# led.net
KiCad netlist of a schematic drawn in Altium Designer
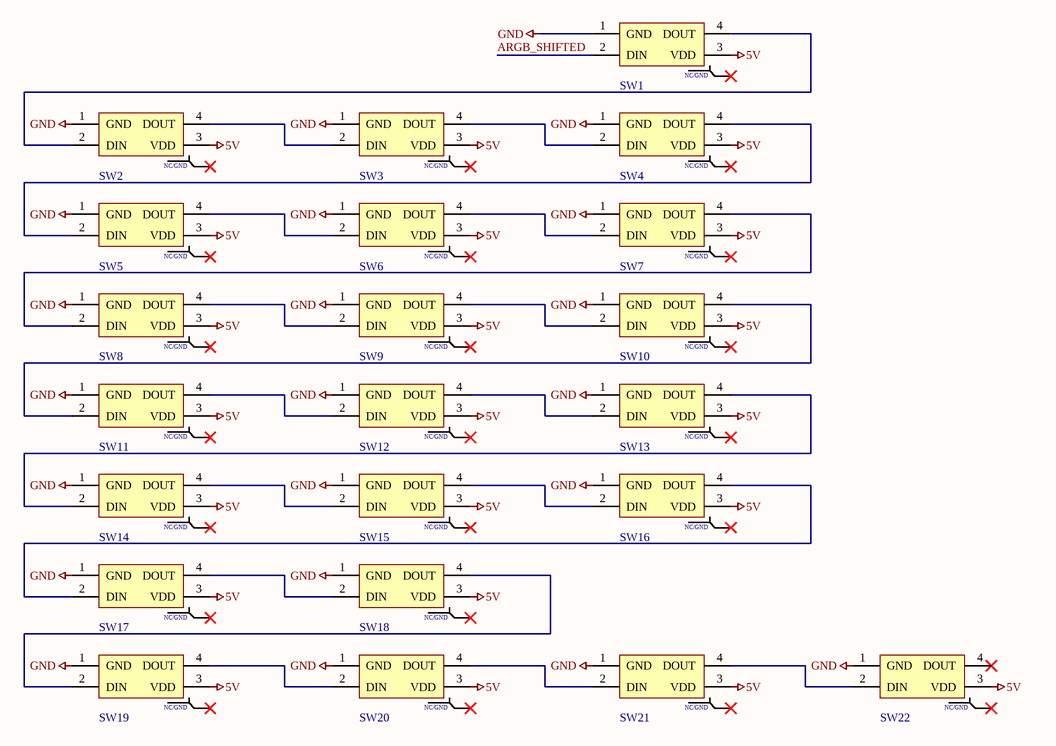
[diagram p0: led.SchDoc]

(export (version "E")
  (design (tool "Eeschema 10.0.6"))
  (components
    (comp (ref "SW1")
      (value "Switch")
      (footprint "Switch")
      (description "Gateron Magnetic Jade Switch")
      (libsource (lib "CHOCO_KEYBOARD") (part "Switch"))
    )
    (comp (ref "SW2")
      (value "Switch")
      (footprint "Switch")
      (description "Gateron Magnetic Jade Switch")
      (libsource (lib "CHOCO_KEYBOARD") (part "Switch"))
    )
    (comp (ref "SW3")
      (value "Switch")
      (footprint "Switch")
      (description "Gateron Magnetic Jade Switch")
      (libsource (lib "CHOCO_KEYBOARD") (part "Switch"))
    )
    (comp (ref "SW4")
      (value "Switch")
      (footprint "Switch")
      (description "Gateron Magnetic Jade Switch")
      (libsource (lib "CHOCO_KEYBOARD") (part "Switch"))
    )
    (comp (ref "SW5")
      (value "Switch")
      (footprint "Switch")
      (description "Gateron Magnetic Jade Switch")
      (libsource (lib "CHOCO_KEYBOARD") (part "Switch"))
    )
    (comp (ref "SW6")
      (value "Switch")
      (footprint "Switch")
      (description "Gateron Magnetic Jade Switch")
      (libsource (lib "CHOCO_KEYBOARD") (part "Switch"))
    )
    (comp (ref "SW7")
      (value "Switch")
      (footprint "Switch")
      (description "Gateron Magnetic Jade Switch")
      (libsource (lib "CHOCO_KEYBOARD") (part "Switch"))
    )
    (comp (ref "SW8")
      (value "Switch")
      (footprint "Switch")
      (description "Gateron Magnetic Jade Switch")
      (libsource (lib "CHOCO_KEYBOARD") (part "Switch"))
    )
    (comp (ref "SW9")
      (value "Switch")
      (footprint "Switch")
      (description "Gateron Magnetic Jade Switch")
      (libsource (lib "CHOCO_KEYBOARD") (part "Switch"))
    )
    (comp (ref "SW10")
      (value "Switch")
      (footprint "Switch")
      (description "Gateron Magnetic Jade Switch")
      (libsource (lib "CHOCO_KEYBOARD") (part "Switch"))
    )
    (comp (ref "SW11")
      (value "Switch")
      (footprint "Switch")
      (description "Gateron Magnetic Jade Switch")
      (libsource (lib "CHOCO_KEYBOARD") (part "Switch"))
    )
    (comp (ref "SW12")
      (value "Switch")
      (footprint "Switch")
      (description "Gateron Magnetic Jade Switch")
      (libsource (lib "CHOCO_KEYBOARD") (part "Switch"))
    )
    (comp (ref "SW13")
      (value "Switch")
      (footprint "Switch")
      (description "Gateron Magnetic Jade Switch")
      (libsource (lib "CHOCO_KEYBOARD") (part "Switch"))
    )
    (comp (ref "SW14")
      (value "Switch")
      (footprint "Switch")
      (description "Gateron Magnetic Jade Switch")
      (libsource (lib "CHOCO_KEYBOARD") (part "Switch"))
    )
    (comp (ref "SW15")
      (value "Switch")
      (footprint "Switch")
      (description "Gateron Magnetic Jade Switch")
      (libsource (lib "CHOCO_KEYBOARD") (part "Switch"))
    )
    (comp (ref "SW16")
      (value "Switch")
      (footprint "Switch")
      (description "Gateron Magnetic Jade Switch")
      (libsource (lib "CHOCO_KEYBOARD") (part "Switch"))
    )
    (comp (ref "SW17")
      (value "Switch")
      (footprint "Switch")
      (description "Gateron Magnetic Jade Switch")
      (libsource (lib "CHOCO_KEYBOARD") (part "Switch"))
    )
    (comp (ref "SW18")
      (value "Switch")
      (footprint "Switch")
      (description "Gateron Magnetic Jade Switch")
      (libsource (lib "CHOCO_KEYBOARD") (part "Switch"))
    )
    (comp (ref "SW19")
      (value "Switch")
      (footprint "Switch")
      (description "Gateron Magnetic Jade Switch")
      (libsource (lib "CHOCO_KEYBOARD") (part "Switch"))
    )
    (comp (ref "SW20")
      (value "Switch")
      (footprint "Switch")
      (description "Gateron Magnetic Jade Switch")
      (libsource (lib "CHOCO_KEYBOARD") (part "Switch"))
    )
    (comp (ref "SW21")
      (value "Switch")
      (footprint "Switch")
      (description "Gateron Magnetic Jade Switch")
      (libsource (lib "CHOCO_KEYBOARD") (part "Switch"))
    )
    (comp (ref "SW22")
      (value "Switch")
      (footprint "Switch")
      (description "Gateron Magnetic Jade Switch")
      (libsource (lib "CHOCO_KEYBOARD") (part "Switch"))
    )
  )
  (nets
    (net (code "1") (name "/ARGB_SHIFTED") (class "Default")
      (node (ref "SW1") (pin "2") (pinfunction "DIN_2") (pintype "passive"))
    )
    (net (code "2") (name "5V") (class "Default")
      (node (ref "SW1") (pin "3") (pinfunction "VDD_3") (pintype "passive"))
      (node (ref "SW10") (pin "3") (pinfunction "VDD_3") (pintype "passive"))
      (node (ref "SW11") (pin "3") (pinfunction "VDD_3") (pintype "passive"))
      (node (ref "SW12") (pin "3") (pinfunction "VDD_3") (pintype "passive"))
      (node (ref "SW13") (pin "3") (pinfunction "VDD_3") (pintype "passive"))
      (node (ref "SW14") (pin "3") (pinfunction "VDD_3") (pintype "passive"))
      (node (ref "SW15") (pin "3") (pinfunction "VDD_3") (pintype "passive"))
      (node (ref "SW16") (pin "3") (pinfunction "VDD_3") (pintype "passive"))
      (node (ref "SW17") (pin "3") (pinfunction "VDD_3") (pintype "passive"))
      (node (ref "SW18") (pin "3") (pinfunction "VDD_3") (pintype "passive"))
      (node (ref "SW19") (pin "3") (pinfunction "VDD_3") (pintype "passive"))
      (node (ref "SW2") (pin "3") (pinfunction "VDD_3") (pintype "passive"))
      (node (ref "SW20") (pin "3") (pinfunction "VDD_3") (pintype "passive"))
      (node (ref "SW21") (pin "3") (pinfunction "VDD_3") (pintype "passive"))
      (node (ref "SW22") (pin "3") (pinfunction "VDD_3") (pintype "passive"))
      (node (ref "SW3") (pin "3") (pinfunction "VDD_3") (pintype "passive"))
      (node (ref "SW4") (pin "3") (pinfunction "VDD_3") (pintype "passive"))
      (node (ref "SW5") (pin "3") (pinfunction "VDD_3") (pintype "passive"))
      (node (ref "SW6") (pin "3") (pinfunction "VDD_3") (pintype "passive"))
      (node (ref "SW7") (pin "3") (pinfunction "VDD_3") (pintype "passive"))
      (node (ref "SW8") (pin "3") (pinfunction "VDD_3") (pintype "passive"))
      (node (ref "SW9") (pin "3") (pinfunction "VDD_3") (pintype "passive"))
    )
    (net (code "3") (name "GND") (class "Default")
      (node (ref "SW1") (pin "1") (pinfunction "GND_1") (pintype "passive"))
      (node (ref "SW10") (pin "1") (pinfunction "GND_1") (pintype "passive"))
      (node (ref "SW11") (pin "1") (pinfunction "GND_1") (pintype "passive"))
      (node (ref "SW12") (pin "1") (pinfunction "GND_1") (pintype "passive"))
      (node (ref "SW13") (pin "1") (pinfunction "GND_1") (pintype "passive"))
      (node (ref "SW14") (pin "1") (pinfunction "GND_1") (pintype "passive"))
      (node (ref "SW15") (pin "1") (pinfunction "GND_1") (pintype "passive"))
      (node (ref "SW16") (pin "1") (pinfunction "GND_1") (pintype "passive"))
      (node (ref "SW17") (pin "1") (pinfunction "GND_1") (pintype "passive"))
      (node (ref "SW18") (pin "1") (pinfunction "GND_1") (pintype "passive"))
      (node (ref "SW19") (pin "1") (pinfunction "GND_1") (pintype "passive"))
      (node (ref "SW2") (pin "1") (pinfunction "GND_1") (pintype "passive"))
      (node (ref "SW20") (pin "1") (pinfunction "GND_1") (pintype "passive"))
      (node (ref "SW21") (pin "1") (pinfunction "GND_1") (pintype "passive"))
      (node (ref "SW22") (pin "1") (pinfunction "GND_1") (pintype "passive"))
      (node (ref "SW3") (pin "1") (pinfunction "GND_1") (pintype "passive"))
      (node (ref "SW4") (pin "1") (pinfunction "GND_1") (pintype "passive"))
      (node (ref "SW5") (pin "1") (pinfunction "GND_1") (pintype "passive"))
      (node (ref "SW6") (pin "1") (pinfunction "GND_1") (pintype "passive"))
      (node (ref "SW7") (pin "1") (pinfunction "GND_1") (pintype "passive"))
      (node (ref "SW8") (pin "1") (pinfunction "GND_1") (pintype "passive"))
      (node (ref "SW9") (pin "1") (pinfunction "GND_1") (pintype "passive"))
    )
    (net (code "4") (name "Net-(SW1-DOUT)") (class "Default")
      (node (ref "SW1") (pin "4") (pinfunction "DOUT_4") (pintype "passive"))
      (node (ref "SW2") (pin "2") (pinfunction "DIN_2") (pintype "passive"))
    )
    (net (code "5") (name "Net-(SW2-DOUT)") (class "Default")
      (node (ref "SW2") (pin "4") (pinfunction "DOUT_4") (pintype "passive"))
      (node (ref "SW3") (pin "2") (pinfunction "DIN_2") (pintype "passive"))
    )
    (net (code "6") (name "Net-(SW3-DOUT)") (class "Default")
      (node (ref "SW3") (pin "4") (pinfunction "DOUT_4") (pintype "passive"))
      (node (ref "SW4") (pin "2") (pinfunction "DIN_2") (pintype "passive"))
    )
    (net (code "7") (name "Net-(SW4-DOUT)") (class "Default")
      (node (ref "SW4") (pin "4") (pinfunction "DOUT_4") (pintype "passive"))
      (node (ref "SW5") (pin "2") (pinfunction "DIN_2") (pintype "passive"))
    )
    (net (code "8") (name "Net-(SW5-DOUT)") (class "Default")
      (node (ref "SW5") (pin "4") (pinfunction "DOUT_4") (pintype "passive"))
      (node (ref "SW6") (pin "2") (pinfunction "DIN_2") (pintype "passive"))
    )
    (net (code "9") (name "Net-(SW6-DOUT)") (class "Default")
      (node (ref "SW6") (pin "4") (pinfunction "DOUT_4") (pintype "passive"))
      (node (ref "SW7") (pin "2") (pinfunction "DIN_2") (pintype "passive"))
    )
    (net (code "10") (name "Net-(SW7-DOUT)") (class "Default")
      (node (ref "SW7") (pin "4") (pinfunction "DOUT_4") (pintype "passive"))
      (node (ref "SW8") (pin "2") (pinfunction "DIN_2") (pintype "passive"))
    )
    (net (code "11") (name "Net-(SW8-DOUT)") (class "Default")
      (node (ref "SW8") (pin "4") (pinfunction "DOUT_4") (pintype "passive"))
      (node (ref "SW9") (pin "2") (pinfunction "DIN_2") (pintype "passive"))
    )
    (net (code "12") (name "Net-(SW10-DIN)") (class "Default")
      (node (ref "SW10") (pin "2") (pinfunction "DIN_2") (pintype "passive"))
      (node (ref "SW9") (pin "4") (pinfunction "DOUT_4") (pintype "passive"))
    )
    (net (code "13") (name "Net-(SW10-DOUT)") (class "Default")
      (node (ref "SW10") (pin "4") (pinfunction "DOUT_4") (pintype "passive"))
      (node (ref "SW11") (pin "2") (pinfunction "DIN_2") (pintype "passive"))
    )
    (net (code "14") (name "Net-(SW11-DOUT)") (class "Default")
      (node (ref "SW11") (pin "4") (pinfunction "DOUT_4") (pintype "passive"))
      (node (ref "SW12") (pin "2") (pinfunction "DIN_2") (pintype "passive"))
    )
    (net (code "15") (name "Net-(SW12-DOUT)") (class "Default")
      (node (ref "SW12") (pin "4") (pinfunction "DOUT_4") (pintype "passive"))
      (node (ref "SW13") (pin "2") (pinfunction "DIN_2") (pintype "passive"))
    )
    (net (code "16") (name "Net-(SW13-DOUT)") (class "Default")
      (node (ref "SW13") (pin "4") (pinfunction "DOUT_4") (pintype "passive"))
      (node (ref "SW14") (pin "2") (pinfunction "DIN_2") (pintype "passive"))
    )
    (net (code "17") (name "Net-(SW14-DOUT)") (class "Default")
      (node (ref "SW14") (pin "4") (pinfunction "DOUT_4") (pintype "passive"))
      (node (ref "SW15") (pin "2") (pinfunction "DIN_2") (pintype "passive"))
    )
    (net (code "18") (name "Net-(SW15-DOUT)") (class "Default")
      (node (ref "SW15") (pin "4") (pinfunction "DOUT_4") (pintype "passive"))
      (node (ref "SW16") (pin "2") (pinfunction "DIN_2") (pintype "passive"))
    )
    (net (code "19") (name "Net-(SW16-DOUT)") (class "Default")
      (node (ref "SW16") (pin "4") (pinfunction "DOUT_4") (pintype "passive"))
      (node (ref "SW17") (pin "2") (pinfunction "DIN_2") (pintype "passive"))
    )
    (net (code "20") (name "Net-(SW17-DOUT)") (class "Default")
      (node (ref "SW17") (pin "4") (pinfunction "DOUT_4") (pintype "passive"))
      (node (ref "SW18") (pin "2") (pinfunction "DIN_2") (pintype "passive"))
    )
    (net (code "21") (name "Net-(SW18-DOUT)") (class "Default")
      (node (ref "SW18") (pin "4") (pinfunction "DOUT_4") (pintype "passive"))
      (node (ref "SW19") (pin "2") (pinfunction "DIN_2") (pintype "passive"))
    )
    (net (code "22") (name "Net-(SW19-DOUT)") (class "Default")
      (node (ref "SW19") (pin "4") (pinfunction "DOUT_4") (pintype "passive"))
      (node (ref "SW20") (pin "2") (pinfunction "DIN_2") (pintype "passive"))
    )
    (net (code "23") (name "Net-(SW20-DOUT)") (class "Default")
      (node (ref "SW20") (pin "4") (pinfunction "DOUT_4") (pintype "passive"))
      (node (ref "SW21") (pin "2") (pinfunction "DIN_2") (pintype "passive"))
    )
    (net (code "24") (name "Net-(SW21-DOUT)") (class "Default")
      (node (ref "SW21") (pin "4") (pinfunction "DOUT_4") (pintype "passive"))
      (node (ref "SW22") (pin "2") (pinfunction "DIN_2") (pintype "passive"))
    )
    (net (code "25") (name "unconnected-(SW1-NC{slash}GND-Pad5)") (class "Default")
      (node (ref "SW1") (pin "5") (pinfunction "NC/GND_5") (pintype "passive+no_connect"))
    )
    (net (code "26") (name "unconnected-(SW2-NC{slash}GND-Pad5)") (class "Default")
      (node (ref "SW2") (pin "5") (pinfunction "NC/GND_5") (pintype "passive+no_connect"))
    )
    (net (code "27") (name "unconnected-(SW3-NC{slash}GND-Pad5)") (class "Default")
      (node (ref "SW3") (pin "5") (pinfunction "NC/GND_5") (pintype "passive+no_connect"))
    )
    (net (code "28") (name "unconnected-(SW4-NC{slash}GND-Pad5)") (class "Default")
      (node (ref "SW4") (pin "5") (pinfunction "NC/GND_5") (pintype "passive+no_connect"))
    )
    (net (code "29") (name "unconnected-(SW5-NC{slash}GND-Pad5)") (class "Default")
      (node (ref "SW5") (pin "5") (pinfunction "NC/GND_5") (pintype "passive+no_connect"))
    )
    (net (code "30") (name "unconnected-(SW6-NC{slash}GND-Pad5)") (class "Default")
      (node (ref "SW6") (pin "5") (pinfunction "NC/GND_5") (pintype "passive+no_connect"))
    )
    (net (code "31") (name "unconnected-(SW7-NC{slash}GND-Pad5)") (class "Default")
      (node (ref "SW7") (pin "5") (pinfunction "NC/GND_5") (pintype "passive+no_connect"))
    )
    (net (code "32") (name "unconnected-(SW8-NC{slash}GND-Pad5)") (class "Default")
      (node (ref "SW8") (pin "5") (pinfunction "NC/GND_5") (pintype "passive+no_connect"))
    )
    (net (code "33") (name "unconnected-(SW9-NC{slash}GND-Pad5)") (class "Default")
      (node (ref "SW9") (pin "5") (pinfunction "NC/GND_5") (pintype "passive+no_connect"))
    )
    (net (code "34") (name "unconnected-(SW10-NC{slash}GND-Pad5)") (class "Default")
      (node (ref "SW10") (pin "5") (pinfunction "NC/GND_5") (pintype "passive+no_connect"))
    )
    (net (code "35") (name "unconnected-(SW11-NC{slash}GND-Pad5)") (class "Default")
      (node (ref "SW11") (pin "5") (pinfunction "NC/GND_5") (pintype "passive+no_connect"))
    )
    (net (code "36") (name "unconnected-(SW12-NC{slash}GND-Pad5)") (class "Default")
      (node (ref "SW12") (pin "5") (pinfunction "NC/GND_5") (pintype "passive+no_connect"))
    )
    (net (code "37") (name "unconnected-(SW13-NC{slash}GND-Pad5)") (class "Default")
      (node (ref "SW13") (pin "5") (pinfunction "NC/GND_5") (pintype "passive+no_connect"))
    )
    (net (code "38") (name "unconnected-(SW14-NC{slash}GND-Pad5)") (class "Default")
      (node (ref "SW14") (pin "5") (pinfunction "NC/GND_5") (pintype "passive+no_connect"))
    )
    (net (code "39") (name "unconnected-(SW15-NC{slash}GND-Pad5)") (class "Default")
      (node (ref "SW15") (pin "5") (pinfunction "NC/GND_5") (pintype "passive+no_connect"))
    )
    (net (code "40") (name "unconnected-(SW16-NC{slash}GND-Pad5)") (class "Default")
      (node (ref "SW16") (pin "5") (pinfunction "NC/GND_5") (pintype "passive+no_connect"))
    )
    (net (code "41") (name "unconnected-(SW17-NC{slash}GND-Pad5)") (class "Default")
      (node (ref "SW17") (pin "5") (pinfunction "NC/GND_5") (pintype "passive+no_connect"))
    )
    (net (code "42") (name "unconnected-(SW18-NC{slash}GND-Pad5)") (class "Default")
      (node (ref "SW18") (pin "5") (pinfunction "NC/GND_5") (pintype "passive+no_connect"))
    )
    (net (code "43") (name "unconnected-(SW19-NC{slash}GND-Pad5)") (class "Default")
      (node (ref "SW19") (pin "5") (pinfunction "NC/GND_5") (pintype "passive+no_connect"))
    )
    (net (code "44") (name "unconnected-(SW20-NC{slash}GND-Pad5)") (class "Default")
      (node (ref "SW20") (pin "5") (pinfunction "NC/GND_5") (pintype "passive+no_connect"))
    )
    (net (code "45") (name "unconnected-(SW21-NC{slash}GND-Pad5)") (class "Default")
      (node (ref "SW21") (pin "5") (pinfunction "NC/GND_5") (pintype "passive+no_connect"))
    )
    (net (code "46") (name "unconnected-(SW22-DOUT-Pad4)") (class "Default")
      (node (ref "SW22") (pin "4") (pinfunction "DOUT_4") (pintype "passive+no_connect"))
    )
    (net (code "47") (name "unconnected-(SW22-NC{slash}GND-Pad5)") (class "Default")
      (node (ref "SW22") (pin "5") (pinfunction "NC/GND_5") (pintype "passive+no_connect"))
    )
  )
)
